# CD-i.net
KiCad netlist of a schematic drawn in EAGLE
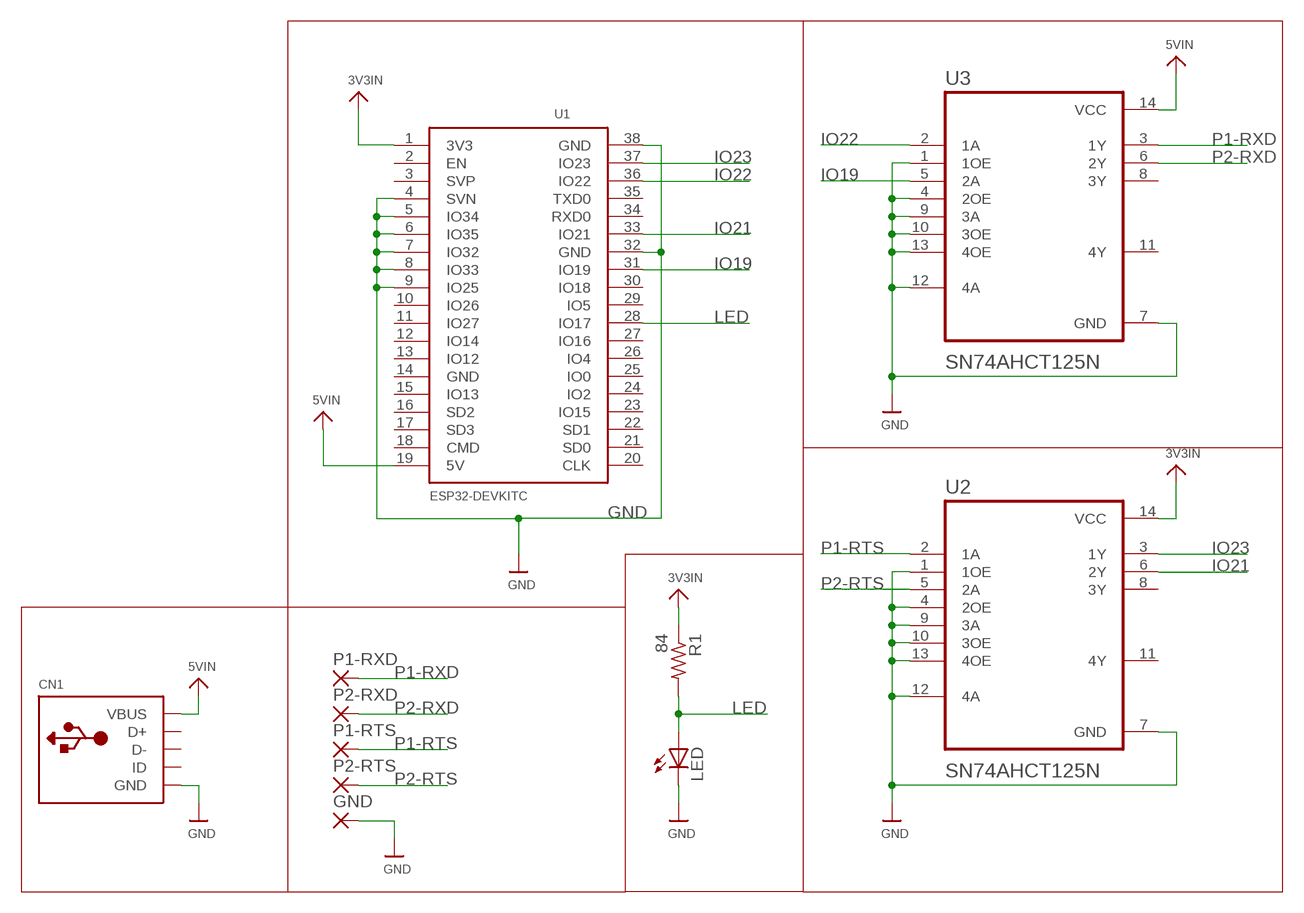
[diagram p0: schematic, sheet 1]

(export (version "E")
  (design (tool "Eeschema 10.0.6"))
  (components
    (comp (ref "CN1")
      (value "USBTHM")
      (footprint "eagle-import:USB-MINIB-THM")
      (libsource (lib "eagle-import") (part "USBTHM"))
    )
    (comp (ref "GND")
      (value "SMD5")
      (footprint "eagle-import:SMD2,54-5,08")
      (libsource (lib "eagle-import") (part "SMD5"))
    )
    (comp (ref "LED")
      (value "LEDCHIPLED_1206")
      (footprint "eagle-import:CHIPLED_1206")
      (libsource (lib "eagle-import") (part "LEDCHIPLED_1206"))
    )
    (comp (ref "P1-RTS")
      (value "SMD5")
      (footprint "eagle-import:SMD2,54-5,08")
      (libsource (lib "eagle-import") (part "SMD5"))
    )
    (comp (ref "P1-RXD")
      (value "SMD5")
      (footprint "eagle-import:SMD2,54-5,08")
      (libsource (lib "eagle-import") (part "SMD5"))
    )
    (comp (ref "P2-RTS")
      (value "SMD5")
      (footprint "eagle-import:SMD2,54-5,08")
      (libsource (lib "eagle-import") (part "SMD5"))
    )
    (comp (ref "P2-RXD")
      (value "SMD5")
      (footprint "eagle-import:SMD2,54-5,08")
      (libsource (lib "eagle-import") (part "SMD5"))
    )
    (comp (ref "R1")
      (value "84")
      (footprint "eagle-import:R1206")
      (libsource (lib "eagle-import") (part "R-US_R1206"))
    )
    (comp (ref "U1")
      (value "ESP32DEVKITC")
      (footprint "eagle-import:ESP32-DEVKITC")
      (libsource (lib "eagle-import") (part "ESP32DEVKITC"))
    )
    (comp (ref "U2")
      (value "SN74AHCT125N")
      (footprint "eagle-import:DIP794W45P254L1969H508Q14")
      (fields (field (name "MF") "Texas Instruments"))
      (libsource (lib "eagle-import") (part "SN74AHCT125N"))
    )
    (comp (ref "U3")
      (value "SN74AHCT125N")
      (footprint "eagle-import:DIP794W45P254L1969H508Q14")
      (fields (field (name "MF") "Texas Instruments"))
      (libsource (lib "eagle-import") (part "SN74AHCT125N"))
    )
  )
  (nets
    (net (code "1") (name "/IO19") (class "Default")
      (node (ref "U1") (pin "31") (pinfunction "IO19_31") (pintype "bidirectional"))
      (node (ref "U3") (pin "5") (pinfunction "2A_5") (pintype "input"))
    )
    (net (code "2") (name "/IO21") (class "Default")
      (node (ref "U1") (pin "33") (pinfunction "IO21_33") (pintype "bidirectional"))
      (node (ref "U2") (pin "6") (pinfunction "2Y_6") (pintype "output"))
    )
    (net (code "3") (name "/IO22") (class "Default")
      (node (ref "U1") (pin "36") (pinfunction "IO22_36") (pintype "bidirectional"))
      (node (ref "U3") (pin "2") (pinfunction "1A_2") (pintype "input"))
    )
    (net (code "4") (name "/IO23") (class "Default")
      (node (ref "U1") (pin "37") (pinfunction "IO23_37") (pintype "bidirectional"))
      (node (ref "U2") (pin "3") (pinfunction "1Y_3") (pintype "output"))
    )
    (net (code "5") (name "/LED") (class "Default")
      (node (ref "LED") (pin "A") (pinfunction "A_A") (pintype "passive"))
      (node (ref "R1") (pin "2") (pinfunction "2_2") (pintype "passive"))
      (node (ref "U1") (pin "28") (pinfunction "IO17_28") (pintype "bidirectional"))
    )
    (net (code "6") (name "/P1-RTS") (class "Default")
      (node (ref "P1-RTS") (pin "1") (pinfunction "P_1") (pintype "passive"))
      (node (ref "U2") (pin "2") (pinfunction "1A_2") (pintype "input"))
    )
    (net (code "7") (name "/P1-RXD") (class "Default")
      (node (ref "P1-RXD") (pin "1") (pinfunction "P_1") (pintype "passive"))
      (node (ref "U3") (pin "3") (pinfunction "1Y_3") (pintype "output"))
    )
    (net (code "8") (name "/P2-RTS") (class "Default")
      (node (ref "P2-RTS") (pin "1") (pinfunction "P_1") (pintype "passive"))
      (node (ref "U2") (pin "5") (pinfunction "2A_5") (pintype "input"))
    )
    (net (code "9") (name "/P2-RXD") (class "Default")
      (node (ref "P2-RXD") (pin "1") (pinfunction "P_1") (pintype "passive"))
      (node (ref "U3") (pin "6") (pinfunction "2Y_6") (pintype "output"))
    )
    (net (code "10") (name "3V3IN") (class "Default")
      (node (ref "R1") (pin "1") (pinfunction "1_1") (pintype "passive"))
      (node (ref "U1") (pin "1") (pinfunction "3V3_1") (pintype "bidirectional"))
      (node (ref "U2") (pin "14") (pinfunction "VCC_14") (pintype "power_in"))
    )
    (net (code "11") (name "5VIN") (class "Default")
      (node (ref "CN1") (pin "VBUS") (pinfunction "VBUS_VBUS") (pintype "power_in"))
      (node (ref "U1") (pin "19") (pinfunction "5V_19") (pintype "bidirectional"))
      (node (ref "U3") (pin "14") (pinfunction "VCC_14") (pintype "power_in"))
    )
    (net (code "12") (name "GND") (class "Default")
      (node (ref "CN1") (pin "GND") (pinfunction "GND_GND") (pintype "power_in"))
      (node (ref "GND") (pin "1") (pinfunction "P_1") (pintype "passive"))
      (node (ref "LED") (pin "C") (pinfunction "C_C") (pintype "passive"))
      (node (ref "U1") (pin "32") (pinfunction "GND_32") (pintype "bidirectional"))
      (node (ref "U1") (pin "38") (pinfunction "GND_38") (pintype "bidirectional"))
      (node (ref "U1") (pin "4") (pinfunction "SVN_4") (pintype "bidirectional"))
      (node (ref "U1") (pin "5") (pinfunction "IO34_5") (pintype "bidirectional"))
      (node (ref "U1") (pin "6") (pinfunction "IO35_6") (pintype "bidirectional"))
      (node (ref "U1") (pin "7") (pinfunction "IO32_7") (pintype "bidirectional"))
      (node (ref "U1") (pin "8") (pinfunction "IO33_8") (pintype "bidirectional"))
      (node (ref "U1") (pin "9") (pinfunction "IO25_9") (pintype "bidirectional"))
      (node (ref "U2") (pin "1") (pinfunction "1OE_1") (pintype "input"))
      (node (ref "U2") (pin "10") (pinfunction "3OE_10") (pintype "input"))
      (node (ref "U2") (pin "12") (pinfunction "4A_12") (pintype "bidirectional"))
      (node (ref "U2") (pin "13") (pinfunction "4OE_13") (pintype "input"))
      (node (ref "U2") (pin "4") (pinfunction "2OE_4") (pintype "input"))
      (node (ref "U2") (pin "7") (pinfunction "GND_7") (pintype "power_in"))
      (node (ref "U2") (pin "9") (pinfunction "3A_9") (pintype "input"))
      (node (ref "U3") (pin "1") (pinfunction "1OE_1") (pintype "input"))
      (node (ref "U3") (pin "10") (pinfunction "3OE_10") (pintype "input"))
      (node (ref "U3") (pin "12") (pinfunction "4A_12") (pintype "bidirectional"))
      (node (ref "U3") (pin "13") (pinfunction "4OE_13") (pintype "input"))
      (node (ref "U3") (pin "4") (pinfunction "2OE_4") (pintype "input"))
      (node (ref "U3") (pin "7") (pinfunction "GND_7") (pintype "power_in"))
      (node (ref "U3") (pin "9") (pinfunction "3A_9") (pintype "input"))
    )
    (net (code "13") (name "unconnected-(CN1-PadD+)") (class "Default")
      (node (ref "CN1") (pin "D+") (pinfunction "D+_D+") (pintype "bidirectional"))
    )
    (net (code "14") (name "unconnected-(CN1-PadD-)") (class "Default")
      (node (ref "CN1") (pin "D-") (pinfunction "D-_D-") (pintype "bidirectional"))
    )
    (net (code "15") (name "unconnected-(CN1-PadID)") (class "Default")
      (node (ref "CN1") (pin "ID") (pinfunction "ID_ID") (pintype "bidirectional"))
    )
    (net (code "16") (name "unconnected-(U1-CLK-Pad20)") (class "Default")
      (node (ref "U1") (pin "20") (pinfunction "CLK_20") (pintype "bidirectional"))
    )
    (net (code "17") (name "unconnected-(U1-CMD-Pad18)") (class "Default")
      (node (ref "U1") (pin "18") (pinfunction "CMD_18") (pintype "bidirectional"))
    )
    (net (code "18") (name "unconnected-(U1-EN-Pad2)") (class "Default")
      (node (ref "U1") (pin "2") (pinfunction "EN_2") (pintype "bidirectional"))
    )
    (net (code "19") (name "unconnected-(U1-GND-Pad14)") (class "Default")
      (node (ref "U1") (pin "14") (pinfunction "GND_14") (pintype "bidirectional"))
    )
    (net (code "20") (name "unconnected-(U1-IO0-Pad25)") (class "Default")
      (node (ref "U1") (pin "25") (pinfunction "IO0_25") (pintype "bidirectional"))
    )
    (net (code "21") (name "unconnected-(U1-IO2-Pad24)") (class "Default")
      (node (ref "U1") (pin "24") (pinfunction "IO2_24") (pintype "bidirectional"))
    )
    (net (code "22") (name "unconnected-(U1-IO4-Pad26)") (class "Default")
      (node (ref "U1") (pin "26") (pinfunction "IO4_26") (pintype "bidirectional"))
    )
    (net (code "23") (name "unconnected-(U1-IO5-Pad29)") (class "Default")
      (node (ref "U1") (pin "29") (pinfunction "IO5_29") (pintype "bidirectional"))
    )
    (net (code "24") (name "unconnected-(U1-IO12-Pad13)") (class "Default")
      (node (ref "U1") (pin "13") (pinfunction "IO12_13") (pintype "bidirectional"))
    )
    (net (code "25") (name "unconnected-(U1-IO13-Pad15)") (class "Default")
      (node (ref "U1") (pin "15") (pinfunction "IO13_15") (pintype "bidirectional"))
    )
    (net (code "26") (name "unconnected-(U1-IO14-Pad12)") (class "Default")
      (node (ref "U1") (pin "12") (pinfunction "IO14_12") (pintype "bidirectional"))
    )
    (net (code "27") (name "unconnected-(U1-IO15-Pad23)") (class "Default")
      (node (ref "U1") (pin "23") (pinfunction "IO15_23") (pintype "bidirectional"))
    )
    (net (code "28") (name "unconnected-(U1-IO16-Pad27)") (class "Default")
      (node (ref "U1") (pin "27") (pinfunction "IO16_27") (pintype "bidirectional"))
    )
    (net (code "29") (name "unconnected-(U1-IO18-Pad30)") (class "Default")
      (node (ref "U1") (pin "30") (pinfunction "IO18_30") (pintype "bidirectional"))
    )
    (net (code "30") (name "unconnected-(U1-IO26-Pad10)") (class "Default")
      (node (ref "U1") (pin "10") (pinfunction "IO26_10") (pintype "bidirectional"))
    )
    (net (code "31") (name "unconnected-(U1-IO27-Pad11)") (class "Default")
      (node (ref "U1") (pin "11") (pinfunction "IO27_11") (pintype "bidirectional"))
    )
    (net (code "32") (name "unconnected-(U1-RXD0-Pad34)") (class "Default")
      (node (ref "U1") (pin "34") (pinfunction "RXD0_34") (pintype "bidirectional"))
    )
    (net (code "33") (name "unconnected-(U1-SD0-Pad21)") (class "Default")
      (node (ref "U1") (pin "21") (pinfunction "SD0_21") (pintype "bidirectional"))
    )
    (net (code "34") (name "unconnected-(U1-SD1-Pad22)") (class "Default")
      (node (ref "U1") (pin "22") (pinfunction "SD1_22") (pintype "bidirectional"))
    )
    (net (code "35") (name "unconnected-(U1-SD2-Pad16)") (class "Default")
      (node (ref "U1") (pin "16") (pinfunction "SD2_16") (pintype "bidirectional"))
    )
    (net (code "36") (name "unconnected-(U1-SD3-Pad17)") (class "Default")
      (node (ref "U1") (pin "17") (pinfunction "SD3_17") (pintype "bidirectional"))
    )
    (net (code "37") (name "unconnected-(U1-SVP-Pad3)") (class "Default")
      (node (ref "U1") (pin "3") (pinfunction "SVP_3") (pintype "bidirectional"))
    )
    (net (code "38") (name "unconnected-(U1-TXD0-Pad35)") (class "Default")
      (node (ref "U1") (pin "35") (pinfunction "TXD0_35") (pintype "bidirectional"))
    )
    (net (code "39") (name "unconnected-(U2-3Y-Pad8)") (class "Default")
      (node (ref "U2") (pin "8") (pinfunction "3Y_8") (pintype "output"))
    )
    (net (code "40") (name "unconnected-(U2-4Y-Pad11)") (class "Default")
      (node (ref "U2") (pin "11") (pinfunction "4Y_11") (pintype "output"))
    )
    (net (code "41") (name "unconnected-(U3-3Y-Pad8)") (class "Default")
      (node (ref "U3") (pin "8") (pinfunction "3Y_8") (pintype "output"))
    )
    (net (code "42") (name "unconnected-(U3-4Y-Pad11)") (class "Default")
      (node (ref "U3") (pin "11") (pinfunction "4Y_11") (pintype "output"))
    )
  )
)
